# Sheet1.net
KiCad netlist of a schematic drawn in Altium Designer
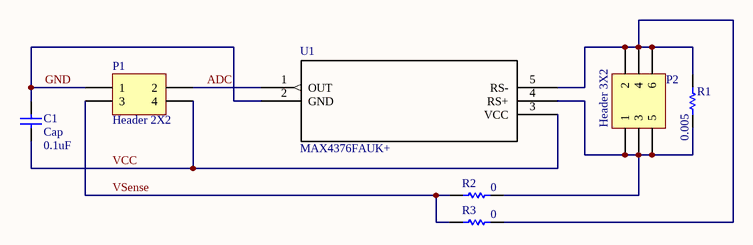
[diagram p0: Sheet1.SchDoc]

(export (version "E")
  (design (tool "Eeschema 10.0.6"))
  (components
    (comp (ref "C1")
      (value "Cap")
      (footprint "C0805")
      (description "Capacitor (Semiconductor SIM Model)")
      (fields (field (name "ALTIUM_VALUE") "0.1uF") (field (name "PUBLISHER") "Altium Limited"))
      (libsource (lib "Miscellaneous Devices") (part "Cap Semi"))
    )
    (comp (ref "P1")
      (value "Header 2X2")
      (footprint "HDR2X2")
      (description "Header, 2-Pin, Dual row")
      (fields (field (name "PUBLISHER") "Altium Limited"))
      (libsource (lib "Miscellaneous Connectors") (part "Header 2X2"))
    )
    (comp (ref "P2")
      (value "Header 3X2")
      (footprint "HDR2X3")
      (description "Header, 3-Pin, Dual row")
      (fields (field (name "PUBLISHER") "Altium Limited"))
      (libsource (lib "Miscellaneous Connectors") (part "Header 3X2"))
    )
    (comp (ref "R1")
      (value "0.005")
      (footprint "C1206")
      (description "Resistor")
      (fields (field (name "Comment") "Res1") (field (name "PUBLISHER") "Altium Limited"))
      (libsource (lib "Miscellaneous Devices") (part "Res1"))
    )
    (comp (ref "R2")
      (value "0")
      (footprint "6-0805_M")
      (description "Resistor")
      (fields (field (name "Comment") "Res1") (field (name "PUBLISHER") "Altium Limited"))
      (libsource (lib "Miscellaneous Devices") (part "Res1"))
    )
    (comp (ref "R3")
      (value "0")
      (footprint "6-0805_M")
      (description "Resistor")
      (fields (field (name "Comment") "Res1") (field (name "PUBLISHER") "Altium Limited"))
      (libsource (lib "Miscellaneous Devices") (part "Res1"))
    )
    (comp (ref "U1")
      (value "MAX4376FAUK+")
      (footprint "21-0057F")
      (description "Imported")
      (fields (field (name "MANUFACTURER_PART_NUMBER") "max4376fauk+"))
      (libsource (lib "Schlib") (part "MAX4376FAUK+"))
    )
  )
  (nets
    (net (code "1") (name "/ADC") (class "Default")
      (node (ref "P1") (pin "2") (pinfunction "2_2") (pintype "passive"))
      (node (ref "U1") (pin "1") (pinfunction "OUT_1") (pintype "output"))
    )
    (net (code "2") (name "/GND") (class "Default")
      (node (ref "C1") (pin "2") (pinfunction "2_2") (pintype "passive"))
      (node (ref "P1") (pin "1") (pinfunction "1_1") (pintype "passive"))
      (node (ref "U1") (pin "2") (pinfunction "GND_2") (pintype "power_in"))
    )
    (net (code "3") (name "/VCC") (class "Default")
      (node (ref "C1") (pin "1") (pinfunction "1_1") (pintype "passive"))
      (node (ref "P1") (pin "4") (pinfunction "4_4") (pintype "passive"))
      (node (ref "U1") (pin "3") (pinfunction "VCC_3") (pintype "power_in"))
    )
    (net (code "4") (name "/VSense") (class "Default")
      (node (ref "P1") (pin "3") (pinfunction "3_3") (pintype "passive"))
      (node (ref "R2") (pin "2") (pinfunction "2_2") (pintype "passive"))
      (node (ref "R3") (pin "2") (pinfunction "2_2") (pintype "passive"))
    )
    (net (code "5") (name "Net-(U1-RS+)") (class "Default")
      (node (ref "P2") (pin "1") (pinfunction "1_1") (pintype "passive"))
      (node (ref "P2") (pin "3") (pinfunction "3_3") (pintype "passive"))
      (node (ref "P2") (pin "5") (pinfunction "5_5") (pintype "passive"))
      (node (ref "R1") (pin "1") (pinfunction "1_1") (pintype "passive"))
      (node (ref "R2") (pin "1") (pinfunction "1_1") (pintype "passive"))
      (node (ref "U1") (pin "4") (pinfunction "RS+_4") (pintype "passive"))
    )
    (net (code "6") (name "Net-(U1-RS-)") (class "Default")
      (node (ref "P2") (pin "2") (pinfunction "2_2") (pintype "passive"))
      (node (ref "P2") (pin "4") (pinfunction "4_4") (pintype "passive"))
      (node (ref "P2") (pin "6") (pinfunction "6_6") (pintype "passive"))
      (node (ref "R1") (pin "2") (pinfunction "2_2") (pintype "passive"))
      (node (ref "R3") (pin "1") (pinfunction "1_1") (pintype "passive"))
      (node (ref "U1") (pin "5") (pinfunction "RS-_5") (pintype "passive"))
    )
  )
)
